# RTC.net
KiCad netlist of a schematic drawn in Altium Designer
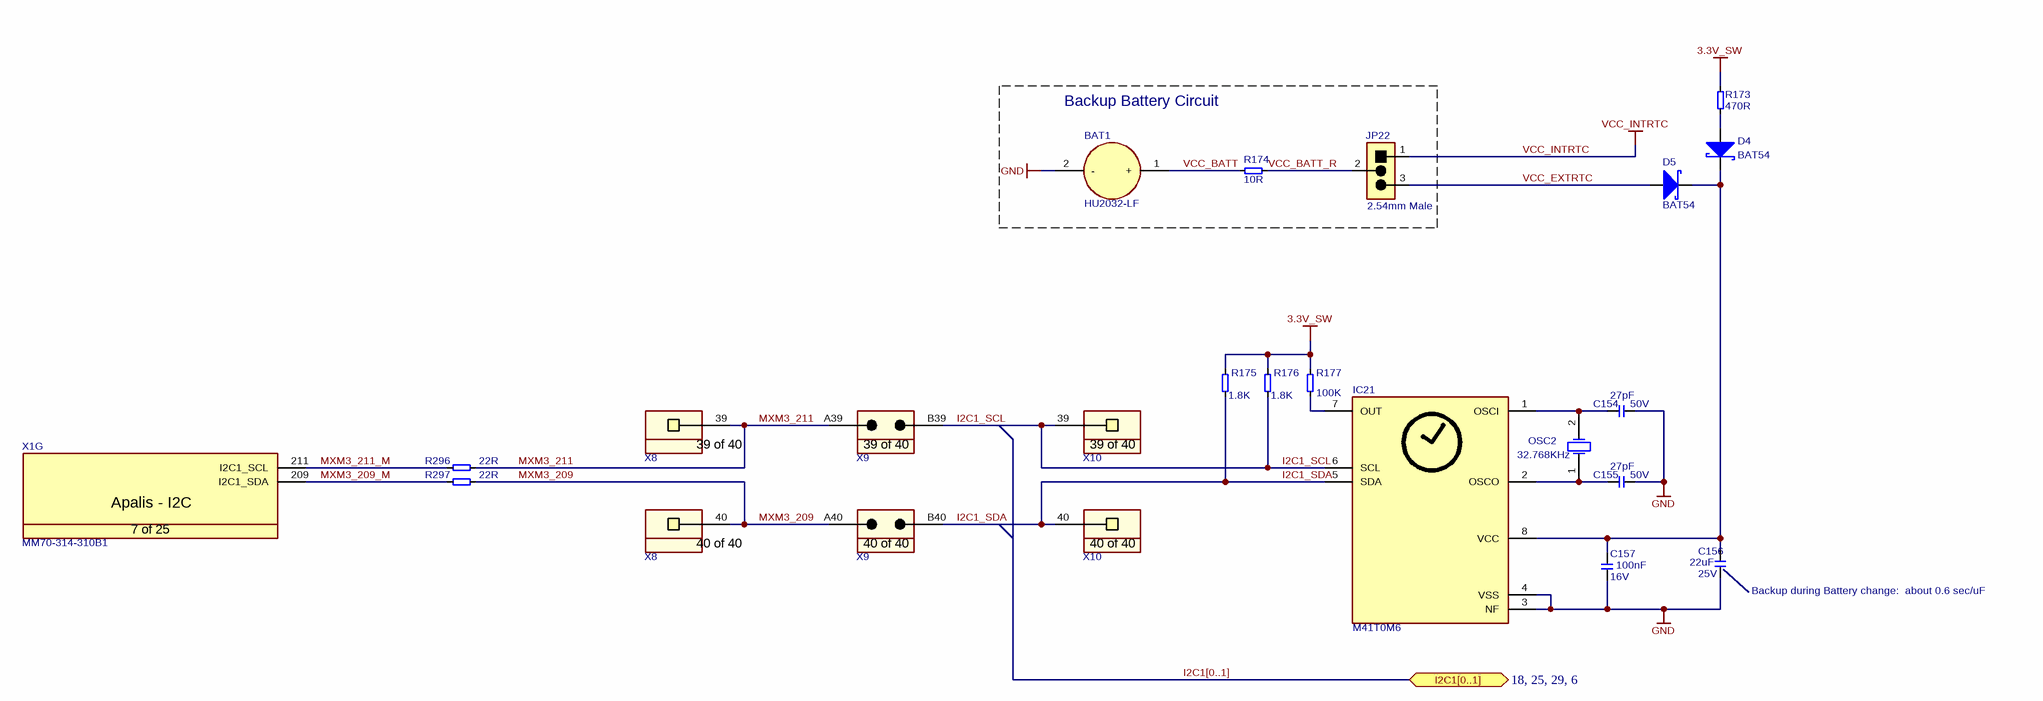
[diagram p0: RTC.SchDoc]

(export (version "E")
  (design (tool "Eeschema 10.0.6"))
  (components
    (comp (ref "BAT1")
      (value "HU2032-LF")
      (footprint "T_Renata_HU2032-LF")
      (description "C2032 Battery Holder")
      (fields (field (name "MANUFACTURER PART NO.") "HU2032-LF"))
      (libsource (lib "Apalis Evaluation Board") (part "BAT-Renata-HU2032-LF"))
    )
    (comp (ref "C154")
      (value "27pF")
      (footprint "T_CAPC0603X33N")
      (description "Capacitor Ceramic NPO 27pF 50V 5% 0603")
      (fields (field (name "TOLERANCE") "5%") (field (name "RATING") "50V"))
      (libsource (lib "Apalis Evaluation Board") (part "C-NPO-27pF-50V-5%-0603"))
    )
    (comp (ref "C155")
      (value "27pF")
      (footprint "T_CAPC0603X33N")
      (description "Capacitor Ceramic NPO 27pF 50V 5% 0603")
      (fields (field (name "TOLERANCE") "5%") (field (name "RATING") "50V"))
      (libsource (lib "Apalis Evaluation Board") (part "C-NPO-27pF-50V-5%-0603"))
    )
    (comp (ref "C156")
      (value "22uF")
      (footprint "CAPC3225X160N")
      (description "Capacitor Ceramic X5R 22uF 25V 20% 1210")
      (fields (field (name "TOLERANCE") "20%") (field (name "RATING") "25V"))
      (libsource (lib "Apalis Evaluation Board") (part "C-X5R-22uF-25V-20%-1210"))
    )
    (comp (ref "C157")
      (value "100nF")
      (footprint "T_CAPC0603X33N")
      (description "Capacitor Ceramic X7R 100nF 16V 10% 0603")
      (fields (field (name "TOLERANCE") "10%") (field (name "RATING") "16V"))
      (libsource (lib "Apalis Evaluation Board") (part "C-X7R-100nF-16V-10%-0603"))
    )
    (comp (ref "D4")
      (value "BAT54")
      (footprint "SOT95P230X110-3N")
      (description "BAT54 Schottky Diode")
      (fields (field (name "MANUFACTURER PART NO.") "BAT54"))
      (libsource (lib "Apalis Evaluation Board") (part "D-Philips-BAT54-Schottky"))
    )
    (comp (ref "D5")
      (value "BAT54")
      (footprint "SOT95P230X110-3N")
      (description "BAT54 Schottky Diode")
      (fields (field (name "MANUFACTURER PART NO.") "BAT54"))
      (libsource (lib "Apalis Evaluation Board") (part "D-Philips-BAT54-Schottky"))
    )
    (comp (ref "IC21")
      (value "M41T0M6")
      (footprint "SOIC127P600X173-8N")
      (description "RTC M41T0M6")
      (fields (field (name "MANUFACTURER PART NO.") "M41T0M6"))
      (libsource (lib "Apalis Evaluation Board") (part "IC-ST-M41T0M6"))
    )
    (comp (ref "JP22")
      (value "826936-3")
      (footprint "T_TYCO_826936-3")
      (description "Jumper, 3-Pin")
      (libsource (lib "Apalis Evaluation Board") (part "CON-Tyco-826936-3-1X3-2.54mm-JP_1"))
    )
    (comp (ref "OSC2")
      (value "32.768KHz")
      (footprint "T_MC_CC4V-T1A")
      (description "Quartz 32.768kHz")
      (fields (field (name "TOLERANCE") "30ppm") (field (name "MANUFACTURER PART NO.") "CC4V-T1A"))
      (libsource (lib "Apalis Evaluation Board") (part "OSC-MC-CC4V-T1A-32.768KHz-30ppm-5x1.9mm"))
    )
    (comp (ref "R173")
      (value "470R")
      (footprint "T_RESC0603X30N")
      (description "Resistor 470 ohm 63mW 5% 0603")
      (fields (field (name "TOLERANCE") "5%"))
      (libsource (lib "Apalis Evaluation Board") (part "R-470R-63mW-5%-0603"))
    )
    (comp (ref "R174")
      (value "10R")
      (footprint "t_RESC0603X30N")
      (description "Resistor 10 ohm 63mW 5% 0603")
      (fields (field (name "TOLERANCE") "5%"))
      (libsource (lib "Apalis Evaluation Board") (part "R-10R-63mW-5%-0603"))
    )
    (comp (ref "R175")
      (value "1.8K")
      (footprint "T_RESC0603X30N")
      (description "Resistor 1.8 Kohm 63mW 5% 0603")
      (fields (field (name "TOLERANCE") "5%"))
      (libsource (lib "Apalis Evaluation Board") (part "R-1.8KR-63mW-5%-0603"))
    )
    (comp (ref "R176")
      (value "1.8K")
      (footprint "T_RESC0603X30N")
      (description "Resistor 1.8 Kohm 63mW 5% 0603")
      (fields (field (name "TOLERANCE") "5%"))
      (libsource (lib "Apalis Evaluation Board") (part "R-1.8KR-63mW-5%-0603"))
    )
    (comp (ref "R177")
      (value "100K")
      (footprint "t_RESC0603X30N")
      (description "Resistor 100 Kohm 63mW 5% 0603")
      (fields (field (name "TOLERANCE") "5%"))
      (libsource (lib "Apalis Evaluation Board") (part "R-100KR-63mW-5%-0603"))
    )
    (comp (ref "R296")
      (value "22R")
      (footprint "RESC1005X40N")
      (description "Resistor 22 ohm 63mW 5% 0402")
      (fields (field (name "TOLERANCE") "5%"))
      (libsource (lib "Apalis Evaluation Board") (part "R-22R-63mW-5%-0402"))
    )
    (comp (ref "R297")
      (value "22R")
      (footprint "RESC1005X40N")
      (description "Resistor 22 ohm 63mW 5% 0402")
      (fields (field (name "TOLERANCE") "5%"))
      (libsource (lib "Apalis Evaluation Board") (part "R-22R-63mW-5%-0402"))
    )
    (comp (ref "X1")
      (value "CON-JAE-MM70-314-310B1-314-0.5mm")
      (footprint "T_JAE_MM70-314-310B1")
      (description "MXM3 Connector")
      (fields (field (name "MANUFACTURER PART NO.") "MM70-314-310B1"))
      (libsource (lib "Apalis Evaluation Board") (part "CON-JAE-MM70-314-310B1-314-0.5mm"))
    )
    (comp (ref "X8")
      (value "SSW-110-01-G-S")
      (footprint "T_Samtec_SSW-110-01-G-S")
      (description "Receptacle Female Socket 1x40 pin 2.54mm pitch")
      (libsource (lib "Apalis Evaluation Board") (part "CON-Samtec-SSW-110-01-G-S"))
    )
    (comp (ref "X9")
      (value "TSW-110-07-G-D")
      (footprint "T_Samtec_TSW-110-07-G-D")
      (description "Header 2x40 pin 2.54mm pitch")
      (libsource (lib "Apalis Evaluation Board") (part "CON-Samtec-TSW-110-07-G-D"))
    )
    (comp (ref "X10")
      (value "SSW-110-01-G-S")
      (footprint "T_Samtec_SSW-110-01-G-S")
      (description "Receptacle Female Socket 1x40 pin 2.54mm pitch")
      (libsource (lib "") (part "CON-Samtec-SSW-110-01-G-S_1"))
    )
  )
  (nets
    (net (code "4") (name "/I2C1_SCL") (class "Default")
      (node (ref "IC21") (pin "6") (pinfunction "SCL_6") (pintype "passive"))
      (node (ref "R176") (pin "1") (pinfunction "1_1") (pintype "passive"))
      (node (ref "X10") (pin "39") (pinfunction "39_39") (pintype "passive"))
      (node (ref "X9") (pin "B39") (pinfunction "B39_B39") (pintype "passive"))
    )
    (net (code "5") (name "/I2C1_SDA") (class "Default")
      (node (ref "IC21") (pin "5") (pinfunction "SDA_5") (pintype "passive"))
      (node (ref "R175") (pin "1") (pinfunction "1_1") (pintype "passive"))
      (node (ref "X10") (pin "40") (pinfunction "40_40") (pintype "passive"))
      (node (ref "X9") (pin "B40") (pinfunction "B40_B40") (pintype "passive"))
    )
    (net (code "6") (name "/MXM3_209") (class "Default")
      (node (ref "R297") (pin "2") (pinfunction "2_2") (pintype "passive"))
      (node (ref "X8") (pin "40") (pinfunction "40_40") (pintype "passive"))
      (node (ref "X9") (pin "A40") (pinfunction "A40_A40") (pintype "passive"))
    )
    (net (code "7") (name "/MXM3_209_M") (class "Default")
      (node (ref "R297") (pin "1") (pinfunction "1_1") (pintype "passive"))
      (node (ref "X1") (pin "209") (pinfunction "I2C1_SDA_209") (pintype "passive"))
    )
    (net (code "8") (name "/MXM3_211") (class "Default")
      (node (ref "R296") (pin "2") (pinfunction "2_2") (pintype "passive"))
      (node (ref "X8") (pin "39") (pinfunction "39_39") (pintype "passive"))
      (node (ref "X9") (pin "A39") (pinfunction "A39_A39") (pintype "passive"))
    )
    (net (code "9") (name "/MXM3_211_M") (class "Default")
      (node (ref "R296") (pin "1") (pinfunction "1_1") (pintype "passive"))
      (node (ref "X1") (pin "211") (pinfunction "I2C1_SCL_211") (pintype "passive"))
    )
    (net (code "10") (name "/VCC_BATT") (class "Default")
      (node (ref "BAT1") (pin "1") (pinfunction "+_1") (pintype "passive"))
      (node (ref "R174") (pin "1") (pinfunction "1_1") (pintype "passive"))
    )
    (net (code "11") (name "/VCC_BATT_R") (class "Default")
      (node (ref "JP22") (pin "2") (pinfunction "2_2") (pintype "passive"))
      (node (ref "R174") (pin "2") (pinfunction "2_2") (pintype "passive"))
    )
    (net (code "12") (name "/VCC_EXTRTC") (class "Default")
      (node (ref "D5") (pin "1") (pinfunction "1_1") (pintype "passive"))
      (node (ref "JP22") (pin "3") (pinfunction "3_3") (pintype "passive"))
    )
    (net (code "13") (name "3.3V_SW") (class "Default")
      (node (ref "R173") (pin "2") (pinfunction "2_2") (pintype "passive"))
      (node (ref "R175") (pin "2") (pinfunction "2_2") (pintype "passive"))
      (node (ref "R176") (pin "2") (pinfunction "2_2") (pintype "passive"))
      (node (ref "R177") (pin "2") (pinfunction "2_2") (pintype "passive"))
    )
    (net (code "14") (name "GND") (class "Default")
      (node (ref "BAT1") (pin "2") (pinfunction "-_2") (pintype "passive"))
      (node (ref "C154") (pin "2") (pinfunction "2_2") (pintype "passive"))
      (node (ref "C155") (pin "2") (pinfunction "2_2") (pintype "passive"))
      (node (ref "C156") (pin "1") (pinfunction "1_1") (pintype "passive"))
      (node (ref "C157") (pin "1") (pinfunction "1_1") (pintype "passive"))
      (node (ref "IC21") (pin "3") (pinfunction "NF_3") (pintype "passive"))
      (node (ref "IC21") (pin "4") (pinfunction "VSS_4") (pintype "passive"))
    )
    (net (code "15") (name "Net-(D4-Pad1)") (class "Default")
      (node (ref "D4") (pin "1") (pinfunction "1_1") (pintype "passive"))
      (node (ref "R173") (pin "1") (pinfunction "1_1") (pintype "passive"))
    )
    (net (code "16") (name "Net-(IC21-OSCI)") (class "Default")
      (node (ref "C154") (pin "1") (pinfunction "1_1") (pintype "passive"))
      (node (ref "IC21") (pin "1") (pinfunction "OSCI_1") (pintype "passive"))
      (node (ref "OSC2") (pin "2") (pinfunction "OSC2_2") (pintype "passive"))
    )
    (net (code "17") (name "Net-(IC21-OSCO)") (class "Default")
      (node (ref "C155") (pin "1") (pinfunction "1_1") (pintype "passive"))
      (node (ref "IC21") (pin "2") (pinfunction "OSCO_2") (pintype "passive"))
      (node (ref "OSC2") (pin "1") (pinfunction "OSC1_1") (pintype "passive"))
    )
    (net (code "18") (name "Net-(IC21-OUT)") (class "Default")
      (node (ref "IC21") (pin "7") (pinfunction "OUT_7") (pintype "passive"))
      (node (ref "R177") (pin "1") (pinfunction "1_1") (pintype "passive"))
    )
    (net (code "19") (name "Net-(IC21-VCC)") (class "Default")
      (node (ref "C156") (pin "2") (pinfunction "2_2") (pintype "passive"))
      (node (ref "C157") (pin "2") (pinfunction "2_2") (pintype "passive"))
      (node (ref "D4") (pin "3") (pinfunction "3_3") (pintype "passive"))
      (node (ref "D5") (pin "3") (pinfunction "3_3") (pintype "passive"))
      (node (ref "IC21") (pin "8") (pinfunction "VCC_8") (pintype "passive"))
    )
    (net (code "20") (name "VCC_INTRTC") (class "Default")
      (node (ref "JP22") (pin "1") (pinfunction "1_1") (pintype "passive"))
    )
  )
)
